# Hexapod_servo_AD.net
KiCad netlist of a schematic drawn in Altium Designer
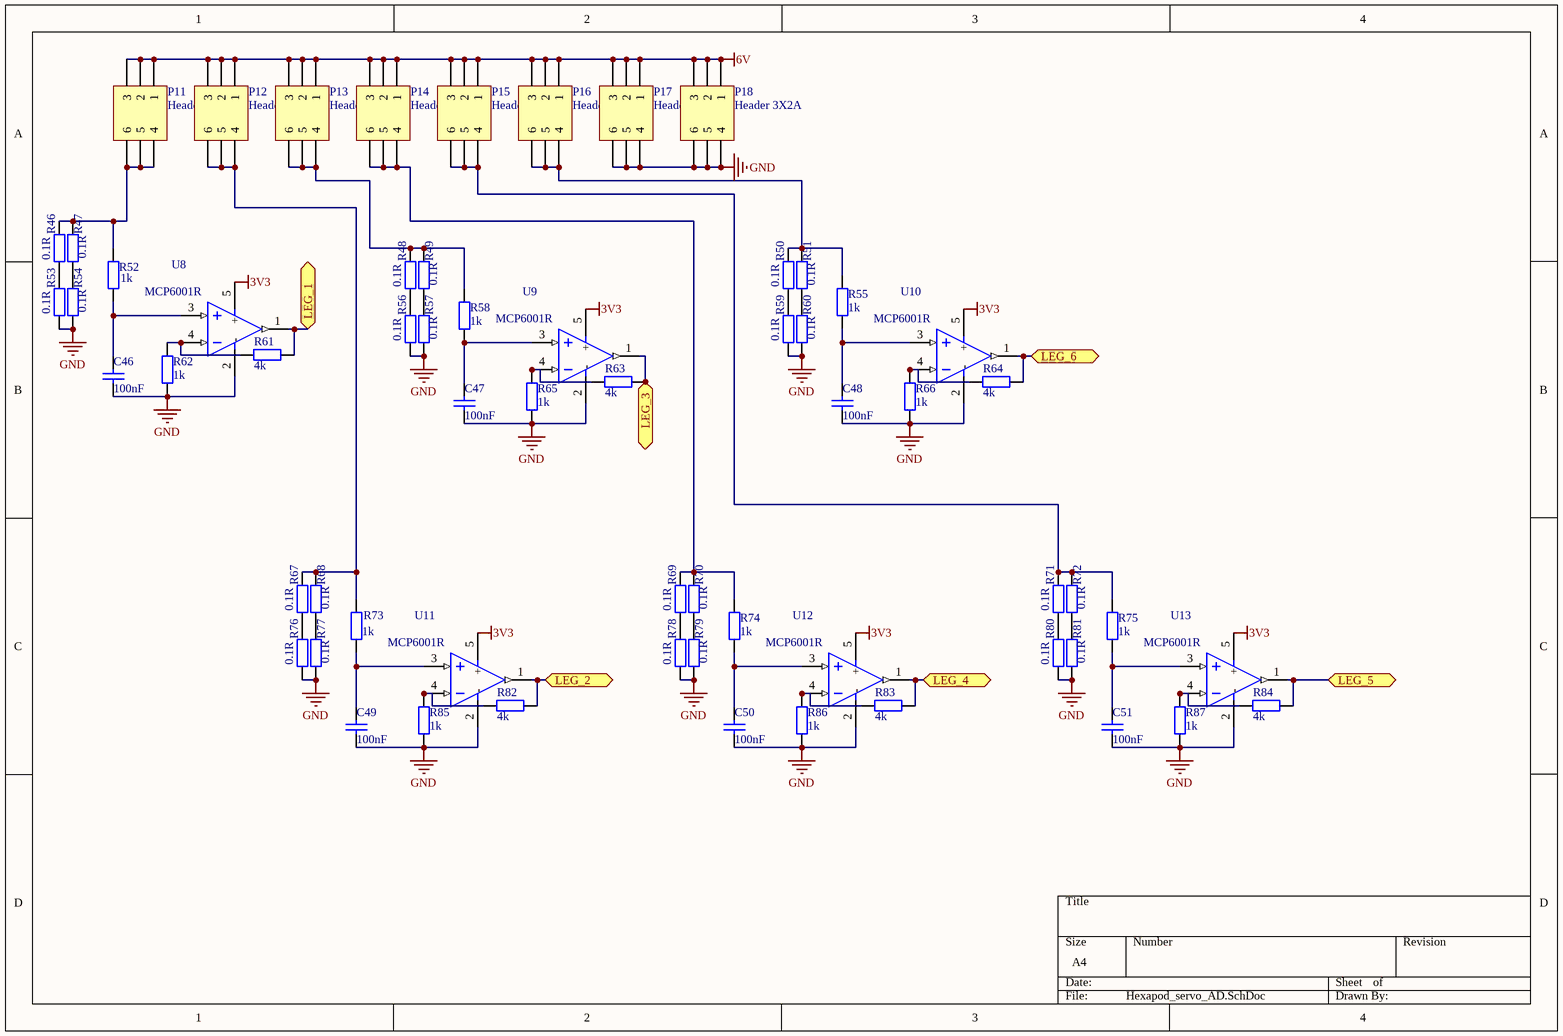
[diagram p0: Hexapod_servo_AD.SchDoc]

(export (version "E")
  (design (tool "Eeschema 10.0.6"))
  (components
    (comp (ref "C46")
      (value "100nF")
      (footprint "FP_0603_CAP_080")
      (description "Capacitor")
      (fields (field (name "PUBLISHER") "Altium Limited"))
      (libsource (lib "Miscellaneous Devices") (part "Cap"))
    )
    (comp (ref "C47")
      (value "100nF")
      (footprint "FP_0603_CAP_080")
      (description "Capacitor")
      (fields (field (name "PUBLISHER") "Altium Limited"))
      (libsource (lib "Miscellaneous Devices") (part "Cap"))
    )
    (comp (ref "C48")
      (value "100nF")
      (footprint "FP_0603_CAP_080")
      (description "Capacitor")
      (fields (field (name "PUBLISHER") "Altium Limited"))
      (libsource (lib "Miscellaneous Devices") (part "Cap"))
    )
    (comp (ref "C49")
      (value "100nF")
      (footprint "FP_0603_CAP_080")
      (description "Capacitor")
      (fields (field (name "PUBLISHER") "Altium Limited"))
      (libsource (lib "Miscellaneous Devices") (part "Cap"))
    )
    (comp (ref "C50")
      (value "100nF")
      (footprint "FP_0603_CAP_080")
      (description "Capacitor")
      (fields (field (name "PUBLISHER") "Altium Limited"))
      (libsource (lib "Miscellaneous Devices") (part "Cap"))
    )
    (comp (ref "C51")
      (value "100nF")
      (footprint "FP_0603_CAP_080")
      (description "Capacitor")
      (fields (field (name "PUBLISHER") "Altium Limited"))
      (libsource (lib "Miscellaneous Devices") (part "Cap"))
    )
    (comp (ref "P11")
      (value "Header 3X2A")
      (footprint "HDR2X3_CEN")
      (description "Header, 3-Pin, Dual row")
      (fields (field (name "PUBLISHER") "Altium Limited"))
      (libsource (lib "Miscellaneous Connectors") (part "Header 3X2A"))
    )
    (comp (ref "P12")
      (value "Header 3X2A")
      (footprint "HDR2X3_CEN")
      (description "Header, 3-Pin, Dual row")
      (fields (field (name "PUBLISHER") "Altium Limited"))
      (libsource (lib "Miscellaneous Connectors") (part "Header 3X2A"))
    )
    (comp (ref "P13")
      (value "Header 3X2A")
      (footprint "HDR2X3_CEN")
      (description "Header, 3-Pin, Dual row")
      (fields (field (name "PUBLISHER") "Altium Limited"))
      (libsource (lib "Miscellaneous Connectors") (part "Header 3X2A"))
    )
    (comp (ref "P14")
      (value "Header 3X2A")
      (footprint "HDR2X3_CEN")
      (description "Header, 3-Pin, Dual row")
      (fields (field (name "PUBLISHER") "Altium Limited"))
      (libsource (lib "Miscellaneous Connectors") (part "Header 3X2A"))
    )
    (comp (ref "P15")
      (value "Header 3X2A")
      (footprint "HDR2X3_CEN")
      (description "Header, 3-Pin, Dual row")
      (fields (field (name "PUBLISHER") "Altium Limited"))
      (libsource (lib "Miscellaneous Connectors") (part "Header 3X2A"))
    )
    (comp (ref "P16")
      (value "Header 3X2A")
      (footprint "HDR2X3_CEN")
      (description "Header, 3-Pin, Dual row")
      (fields (field (name "PUBLISHER") "Altium Limited"))
      (libsource (lib "Miscellaneous Connectors") (part "Header 3X2A"))
    )
    (comp (ref "P17")
      (value "Header 3X2A")
      (footprint "HDR2X3_CEN")
      (description "Header, 3-Pin, Dual row")
      (fields (field (name "PUBLISHER") "Altium Limited"))
      (libsource (lib "Miscellaneous Connectors") (part "Header 3X2A"))
    )
    (comp (ref "P18")
      (value "Header 3X2A")
      (footprint "HDR2X3_CEN")
      (description "Header, 3-Pin, Dual row")
      (fields (field (name "PUBLISHER") "Altium Limited"))
      (libsource (lib "Miscellaneous Connectors") (part "Header 3X2A"))
    )
    (comp (ref "R46")
      (value "0.1R")
      (footprint "FP_0603_RES")
      (description "Resistor")
      (fields (field (name "PUBLISHER") "Altium Limited"))
      (libsource (lib "") (part "Res3_1"))
    )
    (comp (ref "R47")
      (value "0.1R")
      (footprint "FP_0603_RES")
      (description "Resistor")
      (fields (field (name "PUBLISHER") "Altium Limited"))
      (libsource (lib "Miscellaneous Devices") (part "Res3"))
    )
    (comp (ref "R48")
      (value "0.1R")
      (footprint "FP_0603_RES")
      (description "Resistor")
      (fields (field (name "PUBLISHER") "Altium Limited"))
      (libsource (lib "") (part "Res3_1"))
    )
    (comp (ref "R49")
      (value "0.1R")
      (footprint "FP_0603_RES")
      (description "Resistor")
      (fields (field (name "PUBLISHER") "Altium Limited"))
      (libsource (lib "Miscellaneous Devices") (part "Res3"))
    )
    (comp (ref "R50")
      (value "0.1R")
      (footprint "FP_0603_RES")
      (description "Resistor")
      (fields (field (name "PUBLISHER") "Altium Limited"))
      (libsource (lib "") (part "Res3_1"))
    )
    (comp (ref "R51")
      (value "0.1R")
      (footprint "FP_0603_RES")
      (description "Resistor")
      (fields (field (name "PUBLISHER") "Altium Limited"))
      (libsource (lib "Miscellaneous Devices") (part "Res3"))
    )
    (comp (ref "R52")
      (value "1k")
      (footprint "FP_0603_RES")
      (description "Resistor")
      (fields (field (name "PUBLISHER") "Altium Limited"))
      (libsource (lib "") (part "Res3_1"))
    )
    (comp (ref "R53")
      (value "0.1R")
      (footprint "FP_0603_RES")
      (description "Resistor")
      (fields (field (name "PUBLISHER") "Altium Limited"))
      (libsource (lib "") (part "Res3_1"))
    )
    (comp (ref "R54")
      (value "0.1R")
      (footprint "FP_0603_RES")
      (description "Resistor")
      (fields (field (name "PUBLISHER") "Altium Limited"))
      (libsource (lib "Miscellaneous Devices") (part "Res3"))
    )
    (comp (ref "R55")
      (value "1k")
      (footprint "FP_0603_RES")
      (description "Resistor")
      (fields (field (name "PUBLISHER") "Altium Limited"))
      (libsource (lib "") (part "Res3_1"))
    )
    (comp (ref "R56")
      (value "0.1R")
      (footprint "FP_0603_RES")
      (description "Resistor")
      (fields (field (name "PUBLISHER") "Altium Limited"))
      (libsource (lib "") (part "Res3_1"))
    )
    (comp (ref "R57")
      (value "0.1R")
      (footprint "FP_0603_RES")
      (description "Resistor")
      (fields (field (name "PUBLISHER") "Altium Limited"))
      (libsource (lib "Miscellaneous Devices") (part "Res3"))
    )
    (comp (ref "R58")
      (value "1k")
      (footprint "FP_0603_RES")
      (description "Resistor")
      (fields (field (name "PUBLISHER") "Altium Limited"))
      (libsource (lib "") (part "Res3_1"))
    )
    (comp (ref "R59")
      (value "0.1R")
      (footprint "FP_0603_RES")
      (description "Resistor")
      (fields (field (name "PUBLISHER") "Altium Limited"))
      (libsource (lib "") (part "Res3_1"))
    )
    (comp (ref "R60")
      (value "0.1R")
      (footprint "FP_0603_RES")
      (description "Resistor")
      (fields (field (name "PUBLISHER") "Altium Limited"))
      (libsource (lib "Miscellaneous Devices") (part "Res3"))
    )
    (comp (ref "R61")
      (value "4k")
      (footprint "FP_0603_RES")
      (description "Resistor")
      (fields (field (name "PUBLISHER") "Altium Limited"))
      (libsource (lib "Miscellaneous Devices") (part "Res3"))
    )
    (comp (ref "R62")
      (value "1k")
      (footprint "FP_0603_RES")
      (description "Resistor")
      (fields (field (name "PUBLISHER") "Altium Limited"))
      (libsource (lib "") (part "Res3_1"))
    )
    (comp (ref "R63")
      (value "4k")
      (footprint "FP_0603_RES")
      (description "Resistor")
      (fields (field (name "PUBLISHER") "Altium Limited"))
      (libsource (lib "Miscellaneous Devices") (part "Res3"))
    )
    (comp (ref "R64")
      (value "4k")
      (footprint "FP_0603_RES")
      (description "Resistor")
      (fields (field (name "PUBLISHER") "Altium Limited"))
      (libsource (lib "Miscellaneous Devices") (part "Res3"))
    )
    (comp (ref "R65")
      (value "1k")
      (footprint "FP_0603_RES")
      (description "Resistor")
      (fields (field (name "PUBLISHER") "Altium Limited"))
      (libsource (lib "") (part "Res3_1"))
    )
    (comp (ref "R66")
      (value "1k")
      (footprint "FP_0603_RES")
      (description "Resistor")
      (fields (field (name "PUBLISHER") "Altium Limited"))
      (libsource (lib "") (part "Res3_1"))
    )
    (comp (ref "R67")
      (value "0.1R")
      (footprint "FP_0603_RES")
      (description "Resistor")
      (fields (field (name "PUBLISHER") "Altium Limited"))
      (libsource (lib "") (part "Res3_1"))
    )
    (comp (ref "R68")
      (value "0.1R")
      (footprint "FP_0603_RES")
      (description "Resistor")
      (fields (field (name "PUBLISHER") "Altium Limited"))
      (libsource (lib "Miscellaneous Devices") (part "Res3"))
    )
    (comp (ref "R69")
      (value "0.1R")
      (footprint "FP_0603_RES")
      (description "Resistor")
      (fields (field (name "PUBLISHER") "Altium Limited"))
      (libsource (lib "") (part "Res3_1"))
    )
    (comp (ref "R70")
      (value "0.1R")
      (footprint "FP_0603_RES")
      (description "Resistor")
      (fields (field (name "PUBLISHER") "Altium Limited"))
      (libsource (lib "Miscellaneous Devices") (part "Res3"))
    )
    (comp (ref "R71")
      (value "0.1R")
      (footprint "FP_0603_RES")
      (description "Resistor")
      (fields (field (name "PUBLISHER") "Altium Limited"))
      (libsource (lib "") (part "Res3_1"))
    )
    (comp (ref "R72")
      (value "0.1R")
      (footprint "FP_0603_RES")
      (description "Resistor")
      (fields (field (name "PUBLISHER") "Altium Limited"))
      (libsource (lib "Miscellaneous Devices") (part "Res3"))
    )
    (comp (ref "R73")
      (value "1k")
      (footprint "FP_0603_RES")
      (description "Resistor")
      (fields (field (name "PUBLISHER") "Altium Limited"))
      (libsource (lib "") (part "Res3_1"))
    )
    (comp (ref "R74")
      (value "1k")
      (footprint "FP_0603_RES")
      (description "Resistor")
      (fields (field (name "PUBLISHER") "Altium Limited"))
      (libsource (lib "") (part "Res3_1"))
    )
    (comp (ref "R75")
      (value "1k")
      (footprint "FP_0603_RES")
      (description "Resistor")
      (fields (field (name "PUBLISHER") "Altium Limited"))
      (libsource (lib "") (part "Res3_1"))
    )
    (comp (ref "R76")
      (value "0.1R")
      (footprint "FP_0603_RES")
      (description "Resistor")
      (fields (field (name "PUBLISHER") "Altium Limited"))
      (libsource (lib "") (part "Res3_1"))
    )
    (comp (ref "R77")
      (value "0.1R")
      (footprint "FP_0603_RES")
      (description "Resistor")
      (fields (field (name "PUBLISHER") "Altium Limited"))
      (libsource (lib "Miscellaneous Devices") (part "Res3"))
    )
    (comp (ref "R78")
      (value "0.1R")
      (footprint "FP_0603_RES")
      (description "Resistor")
      (fields (field (name "PUBLISHER") "Altium Limited"))
      (libsource (lib "") (part "Res3_1"))
    )
    (comp (ref "R79")
      (value "0.1R")
      (footprint "FP_0603_RES")
      (description "Resistor")
      (fields (field (name "PUBLISHER") "Altium Limited"))
      (libsource (lib "Miscellaneous Devices") (part "Res3"))
    )
    (comp (ref "R80")
      (value "0.1R")
      (footprint "FP_0603_RES")
      (description "Resistor")
      (fields (field (name "PUBLISHER") "Altium Limited"))
      (libsource (lib "") (part "Res3_1"))
    )
    (comp (ref "R81")
      (value "0.1R")
      (footprint "FP_0603_RES")
      (description "Resistor")
      (fields (field (name "PUBLISHER") "Altium Limited"))
      (libsource (lib "Miscellaneous Devices") (part "Res3"))
    )
    (comp (ref "R82")
      (value "4k")
      (footprint "FP_0603_RES")
      (description "Resistor")
      (fields (field (name "PUBLISHER") "Altium Limited"))
      (libsource (lib "Miscellaneous Devices") (part "Res3"))
    )
    (comp (ref "R83")
      (value "4k")
      (footprint "FP_0603_RES")
      (description "Resistor")
      (fields (field (name "PUBLISHER") "Altium Limited"))
      (libsource (lib "Miscellaneous Devices") (part "Res3"))
    )
    (comp (ref "R84")
      (value "4k")
      (footprint "FP_0603_RES")
      (description "Resistor")
      (fields (field (name "PUBLISHER") "Altium Limited"))
      (libsource (lib "Miscellaneous Devices") (part "Res3"))
    )
    (comp (ref "R85")
      (value "1k")
      (footprint "FP_0603_RES")
      (description "Resistor")
      (fields (field (name "PUBLISHER") "Altium Limited"))
      (libsource (lib "") (part "Res3_1"))
    )
    (comp (ref "R86")
      (value "1k")
      (footprint "FP_0603_RES")
      (description "Resistor")
      (fields (field (name "PUBLISHER") "Altium Limited"))
      (libsource (lib "") (part "Res3_1"))
    )
    (comp (ref "R87")
      (value "1k")
      (footprint "FP_0603_RES")
      (description "Resistor")
      (fields (field (name "PUBLISHER") "Altium Limited"))
      (libsource (lib "") (part "Res3_1"))
    )
    (comp (ref "U8")
      (value "MCP6001R")
      (footprint "ANALOG_SOT23-5")
      (libsource (lib "Analog") (part "MCP6001R"))
    )
    (comp (ref "U9")
      (value "MCP6001R")
      (footprint "ANALOG_SOT23-5")
      (libsource (lib "Analog") (part "MCP6001R"))
    )
    (comp (ref "U10")
      (value "MCP6001R")
      (footprint "ANALOG_SOT23-5")
      (libsource (lib "Analog") (part "MCP6001R"))
    )
    (comp (ref "U11")
      (value "MCP6001R")
      (footprint "ANALOG_SOT23-5")
      (libsource (lib "Analog") (part "MCP6001R"))
    )
    (comp (ref "U12")
      (value "MCP6001R")
      (footprint "ANALOG_SOT23-5")
      (libsource (lib "Analog") (part "MCP6001R"))
    )
    (comp (ref "U13")
      (value "MCP6001R")
      (footprint "ANALOG_SOT23-5")
      (libsource (lib "Analog") (part "MCP6001R"))
    )
  )
  (nets
    (net (code "1") (name "/LEG_1") (class "Default")
      (node (ref "R61") (pin "2") (pinfunction "2_2") (pintype "passive"))
      (node (ref "U8") (pin "1") (pinfunction "OUT1_1") (pintype "output"))
    )
    (net (code "2") (name "/LEG_2") (class "Default")
      (node (ref "R82") (pin "2") (pinfunction "2_2") (pintype "passive"))
      (node (ref "U11") (pin "1") (pinfunction "OUT1_1") (pintype "output"))
    )
    (net (code "3") (name "/LEG_3") (class "Default")
      (node (ref "R63") (pin "2") (pinfunction "2_2") (pintype "passive"))
      (node (ref "U9") (pin "1") (pinfunction "OUT1_1") (pintype "output"))
    )
    (net (code "4") (name "/LEG_4") (class "Default")
      (node (ref "R83") (pin "2") (pinfunction "2_2") (pintype "passive"))
      (node (ref "U12") (pin "1") (pinfunction "OUT1_1") (pintype "output"))
    )
    (net (code "5") (name "/LEG_5") (class "Default")
      (node (ref "R84") (pin "2") (pinfunction "2_2") (pintype "passive"))
      (node (ref "U13") (pin "1") (pinfunction "OUT1_1") (pintype "output"))
    )
    (net (code "6") (name "/LEG_6") (class "Default")
      (node (ref "R64") (pin "2") (pinfunction "2_2") (pintype "passive"))
      (node (ref "U10") (pin "1") (pinfunction "OUT1_1") (pintype "output"))
    )
    (net (code "7") (name "3V3") (class "Default")
      (node (ref "U10") (pin "5") (pinfunction "+_5") (pintype "power_in"))
      (node (ref "U11") (pin "5") (pinfunction "+_5") (pintype "power_in"))
      (node (ref "U12") (pin "5") (pinfunction "+_5") (pintype "power_in"))
      (node (ref "U13") (pin "5") (pinfunction "+_5") (pintype "power_in"))
      (node (ref "U8") (pin "5") (pinfunction "+_5") (pintype "power_in"))
      (node (ref "U9") (pin "5") (pinfunction "+_5") (pintype "power_in"))
    )
    (net (code "8") (name "6V") (class "Default")
      (node (ref "P11") (pin "1") (pinfunction "1_1") (pintype "passive"))
      (node (ref "P11") (pin "2") (pinfunction "2_2") (pintype "passive"))
      (node (ref "P11") (pin "3") (pinfunction "3_3") (pintype "passive"))
      (node (ref "P12") (pin "1") (pinfunction "1_1") (pintype "passive"))
      (node (ref "P12") (pin "2") (pinfunction "2_2") (pintype "passive"))
      (node (ref "P12") (pin "3") (pinfunction "3_3") (pintype "passive"))
      (node (ref "P13") (pin "1") (pinfunction "1_1") (pintype "passive"))
      (node (ref "P13") (pin "2") (pinfunction "2_2") (pintype "passive"))
      (node (ref "P13") (pin "3") (pinfunction "3_3") (pintype "passive"))
      (node (ref "P14") (pin "1") (pinfunction "1_1") (pintype "passive"))
      (node (ref "P14") (pin "2") (pinfunction "2_2") (pintype "passive"))
      (node (ref "P14") (pin "3") (pinfunction "3_3") (pintype "passive"))
      (node (ref "P15") (pin "1") (pinfunction "1_1") (pintype "passive"))
      (node (ref "P15") (pin "2") (pinfunction "2_2") (pintype "passive"))
      (node (ref "P15") (pin "3") (pinfunction "3_3") (pintype "passive"))
      (node (ref "P16") (pin "1") (pinfunction "1_1") (pintype "passive"))
      (node (ref "P16") (pin "2") (pinfunction "2_2") (pintype "passive"))
      (node (ref "P16") (pin "3") (pinfunction "3_3") (pintype "passive"))
      (node (ref "P17") (pin "1") (pinfunction "1_1") (pintype "passive"))
      (node (ref "P17") (pin "2") (pinfunction "2_2") (pintype "passive"))
      (node (ref "P17") (pin "3") (pinfunction "3_3") (pintype "passive"))
      (node (ref "P18") (pin "1") (pinfunction "1_1") (pintype "passive"))
      (node (ref "P18") (pin "2") (pinfunction "2_2") (pintype "passive"))
      (node (ref "P18") (pin "3") (pinfunction "3_3") (pintype "passive"))
    )
    (net (code "9") (name "GND") (class "Default")
      (node (ref "C46") (pin "1") (pinfunction "1_1") (pintype "passive"))
      (node (ref "C47") (pin "1") (pinfunction "1_1") (pintype "passive"))
      (node (ref "C48") (pin "1") (pinfunction "1_1") (pintype "passive"))
      (node (ref "C49") (pin "1") (pinfunction "1_1") (pintype "passive"))
      (node (ref "C50") (pin "1") (pinfunction "1_1") (pintype "passive"))
      (node (ref "C51") (pin "1") (pinfunction "1_1") (pintype "passive"))
      (node (ref "P17") (pin "4") (pinfunction "4_4") (pintype "passive"))
      (node (ref "P17") (pin "5") (pinfunction "5_5") (pintype "passive"))
      (node (ref "P17") (pin "6") (pinfunction "6_6") (pintype "passive"))
      (node (ref "P18") (pin "4") (pinfunction "4_4") (pintype "passive"))
      (node (ref "P18") (pin "5") (pinfunction "5_5") (pintype "passive"))
      (node (ref "P18") (pin "6") (pinfunction "6_6") (pintype "passive"))
      (node (ref "R53") (pin "1") (pinfunction "1_1") (pintype "passive"))
      (node (ref "R54") (pin "1") (pinfunction "1_1") (pintype "passive"))
      (node (ref "R56") (pin "1") (pinfunction "1_1") (pintype "passive"))
      (node (ref "R57") (pin "1") (pinfunction "1_1") (pintype "passive"))
      (node (ref "R59") (pin "1") (pinfunction "1_1") (pintype "passive"))
      (node (ref "R60") (pin "1") (pinfunction "1_1") (pintype "passive"))
      (node (ref "R62") (pin "1") (pinfunction "1_1") (pintype "passive"))
      (node (ref "R65") (pin "1") (pinfunction "1_1") (pintype "passive"))
      (node (ref "R66") (pin "1") (pinfunction "1_1") (pintype "passive"))
      (node (ref "R76") (pin "1") (pinfunction "1_1") (pintype "passive"))
      (node (ref "R77") (pin "1") (pinfunction "1_1") (pintype "passive"))
      (node (ref "R78") (pin "1") (pinfunction "1_1") (pintype "passive"))
      (node (ref "R79") (pin "1") (pinfunction "1_1") (pintype "passive"))
      (node (ref "R80") (pin "1") (pinfunction "1_1") (pintype "passive"))
      (node (ref "R81") (pin "1") (pinfunction "1_1") (pintype "passive"))
      (node (ref "R85") (pin "1") (pinfunction "1_1") (pintype "passive"))
      (node (ref "R86") (pin "1") (pinfunction "1_1") (pintype "passive"))
      (node (ref "R87") (pin "1") (pinfunction "1_1") (pintype "passive"))
      (node (ref "U10") (pin "2") (pinfunction "-_2") (pintype "power_in"))
      (node (ref "U11") (pin "2") (pinfunction "-_2") (pintype "power_in"))
      (node (ref "U12") (pin "2") (pinfunction "-_2") (pintype "power_in"))
      (node (ref "U13") (pin "2") (pinfunction "-_2") (pintype "power_in"))
      (node (ref "U8") (pin "2") (pinfunction "-_2") (pintype "power_in"))
      (node (ref "U9") (pin "2") (pinfunction "-_2") (pintype "power_in"))
    )
    (net (code "10") (name "Net-(P11-Pad4)") (class "Default")
      (node (ref "P11") (pin "4") (pinfunction "4_4") (pintype "passive"))
      (node (ref "P11") (pin "5") (pinfunction "5_5") (pintype "passive"))
      (node (ref "P11") (pin "6") (pinfunction "6_6") (pintype "passive"))
      (node (ref "R46") (pin "2") (pinfunction "2_2") (pintype "passive"))
      (node (ref "R47") (pin "2") (pinfunction "2_2") (pintype "passive"))
      (node (ref "R52") (pin "2") (pinfunction "2_2") (pintype "passive"))
    )
    (net (code "11") (name "Net-(P12-Pad4)") (class "Default")
      (node (ref "P12") (pin "4") (pinfunction "4_4") (pintype "passive"))
      (node (ref "P12") (pin "5") (pinfunction "5_5") (pintype "passive"))
      (node (ref "P12") (pin "6") (pinfunction "6_6") (pintype "passive"))
      (node (ref "R67") (pin "2") (pinfunction "2_2") (pintype "passive"))
      (node (ref "R68") (pin "2") (pinfunction "2_2") (pintype "passive"))
      (node (ref "R73") (pin "2") (pinfunction "2_2") (pintype "passive"))
    )
    (net (code "12") (name "Net-(P13-Pad4)") (class "Default")
      (node (ref "P13") (pin "4") (pinfunction "4_4") (pintype "passive"))
      (node (ref "P13") (pin "5") (pinfunction "5_5") (pintype "passive"))
      (node (ref "P13") (pin "6") (pinfunction "6_6") (pintype "passive"))
      (node (ref "R48") (pin "2") (pinfunction "2_2") (pintype "passive"))
      (node (ref "R49") (pin "2") (pinfunction "2_2") (pintype "passive"))
      (node (ref "R58") (pin "2") (pinfunction "2_2") (pintype "passive"))
    )
    (net (code "13") (name "Net-(P14-Pad4)") (class "Default")
      (node (ref "P14") (pin "4") (pinfunction "4_4") (pintype "passive"))
      (node (ref "P14") (pin "5") (pinfunction "5_5") (pintype "passive"))
      (node (ref "P14") (pin "6") (pinfunction "6_6") (pintype "passive"))
      (node (ref "R69") (pin "2") (pinfunction "2_2") (pintype "passive"))
      (node (ref "R70") (pin "2") (pinfunction "2_2") (pintype "passive"))
      (node (ref "R74") (pin "2") (pinfunction "2_2") (pintype "passive"))
    )
    (net (code "14") (name "Net-(P15-Pad4)") (class "Default")
      (node (ref "P15") (pin "4") (pinfunction "4_4") (pintype "passive"))
      (node (ref "P15") (pin "5") (pinfunction "5_5") (pintype "passive"))
      (node (ref "P15") (pin "6") (pinfunction "6_6") (pintype "passive"))
      (node (ref "R71") (pin "2") (pinfunction "2_2") (pintype "passive"))
      (node (ref "R72") (pin "2") (pinfunction "2_2") (pintype "passive"))
      (node (ref "R75") (pin "2") (pinfunction "2_2") (pintype "passive"))
    )
    (net (code "15") (name "Net-(P16-Pad4)") (class "Default")
      (node (ref "P16") (pin "4") (pinfunction "4_4") (pintype "passive"))
      (node (ref "P16") (pin "5") (pinfunction "5_5") (pintype "passive"))
      (node (ref "P16") (pin "6") (pinfunction "6_6") (pintype "passive"))
      (node (ref "R50") (pin "2") (pinfunction "2_2") (pintype "passive"))
      (node (ref "R51") (pin "2") (pinfunction "2_2") (pintype "passive"))
      (node (ref "R55") (pin "2") (pinfunction "2_2") (pintype "passive"))
    )
    (net (code "16") (name "Net-(R46-Pad1)") (class "Default")
      (node (ref "R46") (pin "1") (pinfunction "1_1") (pintype "passive"))
      (node (ref "R53") (pin "2") (pinfunction "2_2") (pintype "passive"))
    )
    (net (code "17") (name "Net-(R47-Pad1)") (class "Default")
      (node (ref "R47") (pin "1") (pinfunction "1_1") (pintype "passive"))
      (node (ref "R54") (pin "2") (pinfunction "2_2") (pintype "passive"))
    )
    (net (code "18") (name "Net-(R48-Pad1)") (class "Default")
      (node (ref "R48") (pin "1") (pinfunction "1_1") (pintype "passive"))
      (node (ref "R56") (pin "2") (pinfunction "2_2") (pintype "passive"))
    )
    (net (code "19") (name "Net-(R49-Pad1)") (class "Default")
      (node (ref "R49") (pin "1") (pinfunction "1_1") (pintype "passive"))
      (node (ref "R57") (pin "2") (pinfunction "2_2") (pintype "passive"))
    )
    (net (code "20") (name "Net-(R50-Pad1)") (class "Default")
      (node (ref "R50") (pin "1") (pinfunction "1_1") (pintype "passive"))
      (node (ref "R59") (pin "2") (pinfunction "2_2") (pintype "passive"))
    )
    (net (code "21") (name "Net-(R51-Pad1)") (class "Default")
      (node (ref "R51") (pin "1") (pinfunction "1_1") (pintype "passive"))
      (node (ref "R60") (pin "2") (pinfunction "2_2") (pintype "passive"))
    )
    (net (code "22") (name "Net-(R67-Pad1)") (class "Default")
      (node (ref "R67") (pin "1") (pinfunction "1_1") (pintype "passive"))
      (node (ref "R76") (pin "2") (pinfunction "2_2") (pintype "passive"))
    )
    (net (code "23") (name "Net-(R68-Pad1)") (class "Default")
      (node (ref "R68") (pin "1") (pinfunction "1_1") (pintype "passive"))
      (node (ref "R77") (pin "2") (pinfunction "2_2") (pintype "passive"))
    )
    (net (code "24") (name "Net-(R69-Pad1)") (class "Default")
      (node (ref "R69") (pin "1") (pinfunction "1_1") (pintype "passive"))
      (node (ref "R78") (pin "2") (pinfunction "2_2") (pintype "passive"))
    )
    (net (code "25") (name "Net-(R70-Pad1)") (class "Default")
      (node (ref "R70") (pin "1") (pinfunction "1_1") (pintype "passive"))
      (node (ref "R79") (pin "2") (pinfunction "2_2") (pintype "passive"))
    )
    (net (code "26") (name "Net-(R71-Pad1)") (class "Default")
      (node (ref "R71") (pin "1") (pinfunction "1_1") (pintype "passive"))
      (node (ref "R80") (pin "2") (pinfunction "2_2") (pintype "passive"))
    )
    (net (code "27") (name "Net-(R72-Pad1)") (class "Default")
      (node (ref "R72") (pin "1") (pinfunction "1_1") (pintype "passive"))
      (node (ref "R81") (pin "2") (pinfunction "2_2") (pintype "passive"))
    )
    (net (code "28") (name "Net-(U8-IN1+)") (class "Default")
      (node (ref "C46") (pin "2") (pinfunction "2_2") (pintype "passive"))
      (node (ref "R52") (pin "1") (pinfunction "1_1") (pintype "passive"))
      (node (ref "U8") (pin "3") (pinfunction "IN1+_3") (pintype "input"))
    )
    (net (code "29") (name "Net-(U8-IN1-)") (class "Default")
      (node (ref "R61") (pin "1") (pinfunction "1_1") (pintype "passive"))
      (node (ref "R62") (pin "2") (pinfunction "2_2") (pintype "passive"))
      (node (ref "U8") (pin "4") (pinfunction "IN1-_4") (pintype "input"))
    )
    (net (code "30") (name "Net-(U9-IN1+)") (class "Default")
      (node (ref "C47") (pin "2") (pinfunction "2_2") (pintype "passive"))
      (node (ref "R58") (pin "1") (pinfunction "1_1") (pintype "passive"))
      (node (ref "U9") (pin "3") (pinfunction "IN1+_3") (pintype "input"))
    )
    (net (code "31") (name "Net-(U9-IN1-)") (class "Default")
      (node (ref "R63") (pin "1") (pinfunction "1_1") (pintype "passive"))
      (node (ref "R65") (pin "2") (pinfunction "2_2") (pintype "passive"))
      (node (ref "U9") (pin "4") (pinfunction "IN1-_4") (pintype "input"))
    )
    (net (code "32") (name "Net-(U10-IN1+)") (class "Default")
      (node (ref "C48") (pin "2") (pinfunction "2_2") (pintype "passive"))
      (node (ref "R55") (pin "1") (pinfunction "1_1") (pintype "passive"))
      (node (ref "U10") (pin "3") (pinfunction "IN1+_3") (pintype "input"))
    )
    (net (code "33") (name "Net-(U10-IN1-)") (class "Default")
      (node (ref "R64") (pin "1") (pinfunction "1_1") (pintype "passive"))
      (node (ref "R66") (pin "2") (pinfunction "2_2") (pintype "passive"))
      (node (ref "U10") (pin "4") (pinfunction "IN1-_4") (pintype "input"))
    )
    (net (code "34") (name "Net-(U11-IN1+)") (class "Default")
      (node (ref "C49") (pin "2") (pinfunction "2_2") (pintype "passive"))
      (node (ref "R73") (pin "1") (pinfunction "1_1") (pintype "passive"))
      (node (ref "U11") (pin "3") (pinfunction "IN1+_3") (pintype "input"))
    )
    (net (code "35") (name "Net-(U11-IN1-)") (class "Default")
      (node (ref "R82") (pin "1") (pinfunction "1_1") (pintype "passive"))
      (node (ref "R85") (pin "2") (pinfunction "2_2") (pintype "passive"))
      (node (ref "U11") (pin "4") (pinfunction "IN1-_4") (pintype "input"))
    )
    (net (code "36") (name "Net-(U12-IN1+)") (class "Default")
      (node (ref "C50") (pin "2") (pinfunction "2_2") (pintype "passive"))
      (node (ref "R74") (pin "1") (pinfunction "1_1") (pintype "passive"))
      (node (ref "U12") (pin "3") (pinfunction "IN1+_3") (pintype "input"))
    )
    (net (code "37") (name "Net-(U12-IN1-)") (class "Default")
      (node (ref "R83") (pin "1") (pinfunction "1_1") (pintype "passive"))
      (node (ref "R86") (pin "2") (pinfunction "2_2") (pintype "passive"))
      (node (ref "U12") (pin "4") (pinfunction "IN1-_4") (pintype "input"))
    )
    (net (code "38") (name "Net-(U13-IN1+)") (class "Default")
      (node (ref "C51") (pin "2") (pinfunction "2_2") (pintype "passive"))
      (node (ref "R75") (pin "1") (pinfunction "1_1") (pintype "passive"))
      (node (ref "U13") (pin "3") (pinfunction "IN1+_3") (pintype "input"))
    )
    (net (code "39") (name "Net-(U13-IN1-)") (class "Default")
      (node (ref "R84") (pin "1") (pinfunction "1_1") (pintype "passive"))
      (node (ref "R87") (pin "2") (pinfunction "2_2") (pintype "passive"))
      (node (ref "U13") (pin "4") (pinfunction "IN1-_4") (pintype "input"))
    )
  )
)
